# schematic.net
KiCad netlist of a schematic drawn in Altium Designer
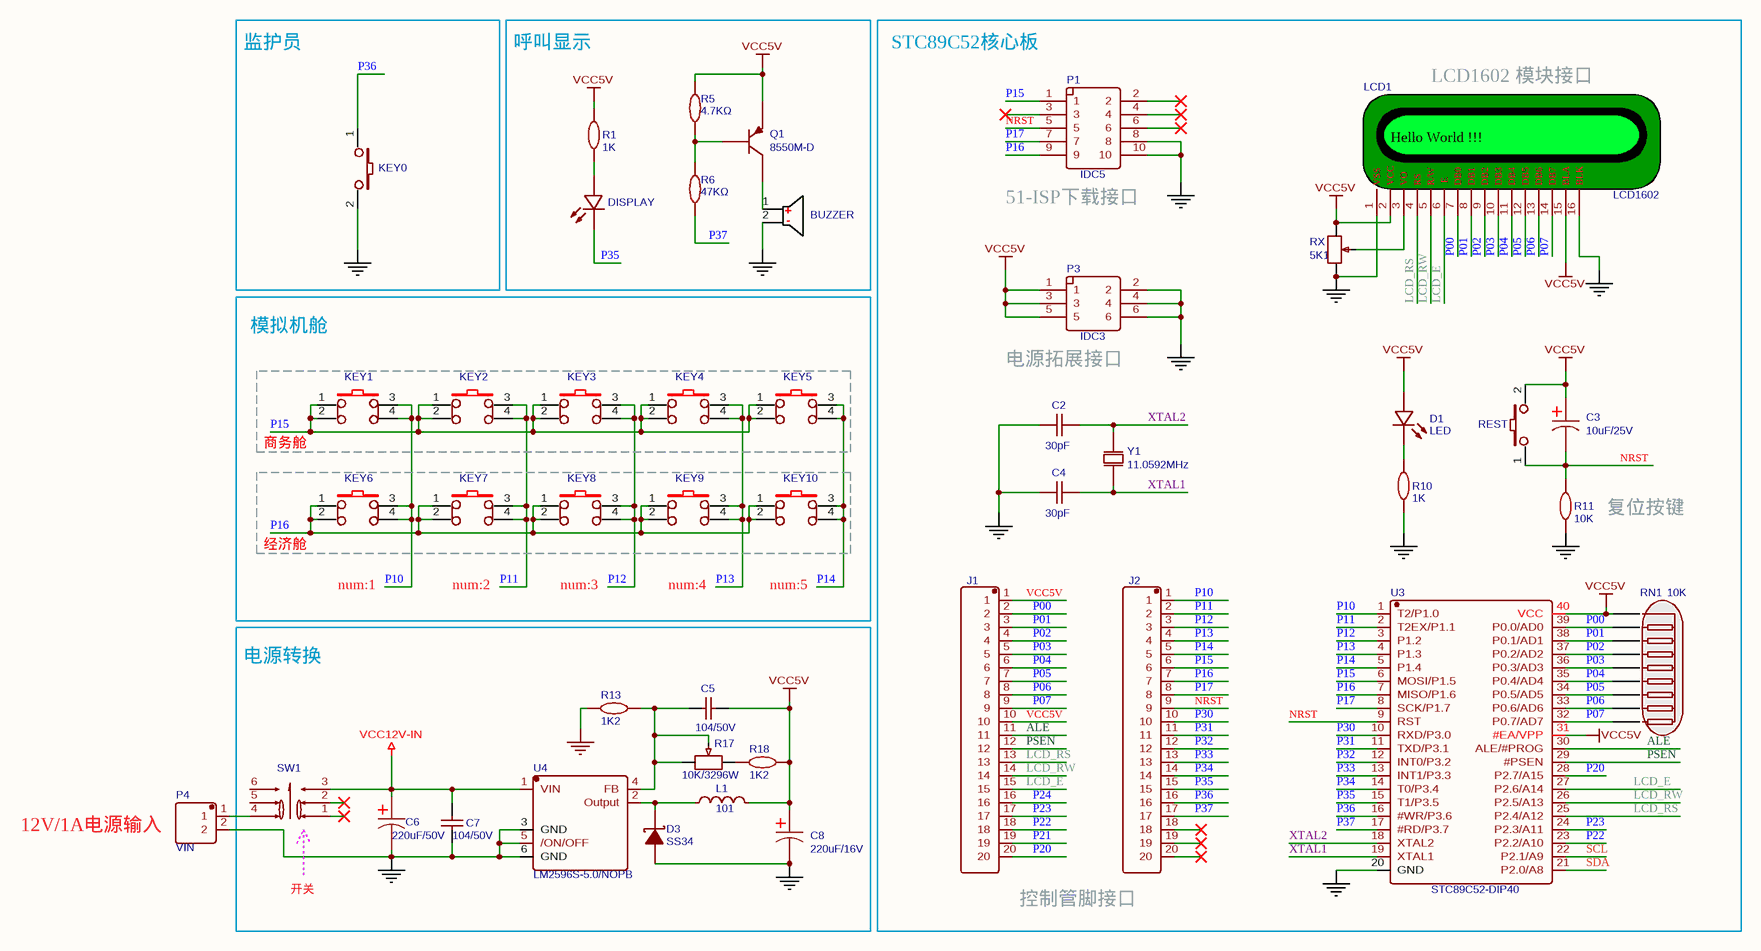
[diagram p0: schematic.schdoc]

(export (version "E")
  (design (tool "Eeschema 10.0.6"))
  (components
    (comp (ref "BUZZER")
      (value "C194267")
      (footprint "BEEP-TH_BD9.1-P5.00-D0.6-L-FD")
      (fields (field (name "CONTRIBUTOR") "LCSC"))
      (libsource (lib "altium-import") (part "root_0_C194267_"))
    )
    (comp (ref "C2")
      (value "30pF")
      (footprint "C0805")
      (fields
        (field (name "BOM_MANUFACTURER PART") "0805N220J500")
        (field (name "BOM_SUPPLIER PART") "C123642")
        (field (name "CONTRIBUTOR") "LCSC")
      )
      (libsource (lib "altium-import") (part "root_0_22pF_"))
    )
    (comp (ref "C3")
      (value "10uF/25V")
      (footprint "RAD6.3")
      (fields
        (field (name "BOM_SUPPLIER PART") "C140381")
        (field (name "BOM_MANUFACTURER PART") "CA45-B-10V-100uF-M")
        (field (name "CONTRIBUTOR") "LCSC")
      )
      (libsource (lib "Project") (part "100uF"))
    )
    (comp (ref "C4")
      (value "30pF")
      (footprint "C0805")
      (fields
        (field (name "BOM_MANUFACTURER PART") "0805N220J500")
        (field (name "BOM_SUPPLIER PART") "C123642")
        (field (name "CONTRIBUTOR") "LCSC")
      )
      (libsource (lib "altium-import") (part "root_0_22pF_"))
    )
    (comp (ref "C5")
      (value "104/50V")
      (footprint "C_0805")
      (fields
        (field (name "BOM_MANUFACTURER PART") "0805F104M500NT")
        (field (name "BOM_SUPPLIER PART") "C28378")
        (field (name "CONTRIBUTOR") "MrWangs")
      )
      (libsource (lib "altium-import") (part "root_0_100nF_"))
    )
    (comp (ref "C6")
      (value "220uF/50V")
      (footprint "RAD6.3")
      (fields
        (field (name "BOM_SUPPLIER PART") "C140381")
        (field (name "BOM_MANUFACTURER PART") "CA45-B-10V-100uF-M")
        (field (name "CONTRIBUTOR") "LCSC")
      )
      (libsource (lib "Project") (part "100uF"))
    )
    (comp (ref "C7")
      (value "104/50V")
      (footprint "C_0805")
      (fields
        (field (name "BOM_MANUFACTURER PART") "0805F104M500NT")
        (field (name "BOM_SUPPLIER PART") "C28378")
        (field (name "CONTRIBUTOR") "MrWangs")
      )
      (libsource (lib "altium-import") (part "root_3_100nF_"))
    )
    (comp (ref "C8")
      (value "220uF/16V")
      (footprint "CASE-B_3528")
      (fields
        (field (name "BOM_SUPPLIER PART") "C140381")
        (field (name "BOM_MANUFACTURER PART") "CA45-B-10V-100uF-M")
        (field (name "CONTRIBUTOR") "LCSC")
      )
      (libsource (lib "Project") (part "100uF"))
    )
    (comp (ref "D1")
      (value "LED")
      (footprint "LED-0805")
      (fields
        (field (name "BOM_MANUFACTURER PART") "whiteLEDSMD")
        (field (name "BOM_SUPPLIER PART") "C34499")
      )
      (libsource (lib "altium-import") (part "root_3_LEDSMD_"))
    )
    (comp (ref "D3")
      (value "SS34")
      (footprint "DO-214AC")
      (fields (field (name "BOM_SUPPLIER PART") "C266553") (field (name "CONTRIBUTOR") "LCSC"))
      (libsource (lib "altium-import") (part "root_1_SS34_C266553_"))
    )
    (comp (ref "DISPLAY")
      (value "HQ17-2102UWC")
      (footprint "LED0805-RD")
      (fields (field (name "BOM_SUPPLIER PART") "C154480") (field (name "CONTRIBUTOR") "LCSC"))
      (libsource (lib "altium-import") (part "root_1_HQ17-2102UWC_"))
    )
    (comp (ref "J1")
      (value "220S-1*20P H=8.5MM Ytype Gold-plated")
      (footprint "HDR-TH_20P-P2.54-V")
      (fields (field (name "BOM_SUPPLIER PART") "C124410") (field (name "CONTRIBUTOR") "LCSC"))
      (libsource (lib "altium-import") (part "root_0_220S-1*20P H=8.5MM Ytype Gold-plated_"))
    )
    (comp (ref "J2")
      (value "220S-1*20P H=8.5MM Ytype Gold-plated")
      (footprint "HDR-TH_20P-P2.54-V")
      (fields (field (name "BOM_SUPPLIER PART") "C124410") (field (name "CONTRIBUTOR") "LCSC"))
      (libsource (lib "altium-import") (part "root_0_220S-1*20P H=8.5MM Ytype Gold-plated_"))
    )
    (comp (ref "KEY0")
      (value "Switch3x4x2")
      (footprint "KEY-3.0*4.0")
      (fields (field (name "BOM_SUPPLIER PART") "C26638"))
      (libsource (lib "altium-import") (part "root_3_Switch3x4x2_"))
    )
    (comp (ref "KEY1")
      (value "12*12*5.5")
      (footprint "KEY-12*12-2")
      (fields (field (name "BOM_SUPPLIER PART") "C58359"))
      (libsource (lib "altium-import") (part "root_0_12*12*5.5_"))
    )
    (comp (ref "KEY2")
      (value "12*12*5.5")
      (footprint "KEY-12*12-2")
      (fields (field (name "BOM_SUPPLIER PART") "C58359"))
      (libsource (lib "altium-import") (part "root_0_12*12*5.5_"))
    )
    (comp (ref "KEY3")
      (value "12*12*5.5")
      (footprint "KEY-12*12-2")
      (fields (field (name "BOM_SUPPLIER PART") "C58359"))
      (libsource (lib "altium-import") (part "root_0_12*12*5.5_"))
    )
    (comp (ref "KEY4")
      (value "12*12*5.5")
      (footprint "KEY-12*12-2")
      (fields (field (name "BOM_SUPPLIER PART") "C58359"))
      (libsource (lib "altium-import") (part "root_0_12*12*5.5_"))
    )
    (comp (ref "KEY5")
      (value "12*12*5.5")
      (footprint "KEY-12*12-2")
      (fields (field (name "BOM_SUPPLIER PART") "C58359"))
      (libsource (lib "altium-import") (part "root_0_12*12*5.5_"))
    )
    (comp (ref "KEY6")
      (value "12*12*5.5")
      (footprint "KEY-12*12-2")
      (fields (field (name "BOM_SUPPLIER PART") "C58359"))
      (libsource (lib "altium-import") (part "root_0_12*12*5.5_"))
    )
    (comp (ref "KEY7")
      (value "12*12*5.5")
      (footprint "KEY-12*12-2")
      (fields (field (name "BOM_SUPPLIER PART") "C58359"))
      (libsource (lib "altium-import") (part "root_0_12*12*5.5_"))
    )
    (comp (ref "KEY8")
      (value "12*12*5.5")
      (footprint "KEY-12*12-2")
      (fields (field (name "BOM_SUPPLIER PART") "C58359"))
      (libsource (lib "altium-import") (part "root_0_12*12*5.5_"))
    )
    (comp (ref "KEY9")
      (value "12*12*5.5")
      (footprint "KEY-12*12-2")
      (fields (field (name "BOM_SUPPLIER PART") "C58359"))
      (libsource (lib "altium-import") (part "root_0_12*12*5.5_"))
    )
    (comp (ref "KEY10")
      (value "12*12*5.5")
      (footprint "KEY-12*12-2")
      (fields (field (name "BOM_SUPPLIER PART") "C58359"))
      (libsource (lib "altium-import") (part "root_0_12*12*5.5_"))
    )
    (comp (ref "L1")
      (value "101")
      (footprint "L-101-3A-SWB")
      (fields
        (field (name "BOM_MANUFACTURER PART") "BLM18RK102SN1D")
        (field (name "BOM_SUPPLIER PART") "C88986")
      )
      (libsource (lib "STM32F429BIT6_LIBRARY") (part "BLM18RK102SN1D"))
    )
    (comp (ref "LCD1")
      (value "LCD1602")
      (footprint "LCD1602")
      (fields
        (field (name "BOM_MANUFACTURER PART") "LCM1602K-NSW-BBW")
        (field (name "BOM_SUPPLIER PART") "C83275")
        (field (name "CONTRIBUTOR") "whwqm")
      )
      (libsource (lib "AT89S52核心板") (part "LCD1602"))
    )
    (comp (ref "P1")
      (value "IDC5")
      (footprint "IDC-TH_Z-231012810106")
      (fields
        (field (name "BOM_MANUFACTURER PART") "Z-231012810106")
        (field (name "BOM_SUPPLIER PART") "C93705")
      )
      (libsource (lib "altium-import") (part "root_0_Z-231012810106_"))
    )
    (comp (ref "P3")
      (value "IDC3")
      (footprint "IDC-TH_6P-P2.54_300R-6P")
      (fields
        (field (name "BOM_MANUFACTURER PART") "300R-6P")
        (field (name "BOM_SUPPLIER PART") "C146629")
        (field (name "CONTRIBUTOR") "LCSC")
      )
      (libsource (lib "altium-import") (part "root_0_300R-6P_"))
    )
    (comp (ref "P4")
      (value "VIN")
      (footprint "WJ2EDGR-5.08-2P")
      (fields
        (field (name "BOM_SUPPLIER PART") "C168673")
        (field (name "BOM_MANUFACTURER PART") "68000-102HLF")
        (field (name "CONTRIBUTOR") "LCSC")
      )
      (libsource (lib "MySheetLib") (part "WJ2EDGRC-5.08-2P"))
    )
    (comp (ref "Q1")
      (value "8550M-D")
      (footprint "SOT-23-3")
      (fields (field (name "BOM_SUPPLIER PART") "C305456") (field (name "CONTRIBUTOR") "LCSC"))
      (libsource (lib "Sheet_1") (part "8550M-D"))
    )
    (comp (ref "R1")
      (value "1K")
      (footprint "R0805")
      (fields
        (field (name "BOM_MANUFACTURER PART") "RK73H2ATTD1001F")
        (field (name "BOM_SUPPLIER PART") "C160065")
        (field (name "CONTRIBUTOR") "LCSC")
      )
      (libsource (lib "altium-import") (part "root_1_1K_"))
    )
    (comp (ref "R5")
      (value "4.7KΩ")
      (footprint "0805_R")
      (fields
        (field (name "BOM_SUPPLIER PART") "C237122")
        (field (name "BOM_MANUFACTURER PART") "RMCF0805FT100R")
        (field (name "CONTRIBUTOR") "MrWangs")
      )
      (libsource (lib "Project") (part "100"))
    )
    (comp (ref "R6")
      (value "47KΩ")
      (footprint "0805_R")
      (fields
        (field (name "BOM_SUPPLIER PART") "C237122")
        (field (name "BOM_MANUFACTURER PART") "RMCF0805FT100R")
        (field (name "CONTRIBUTOR") "MrWangs")
      )
      (libsource (lib "Project") (part "100"))
    )
    (comp (ref "R10")
      (value "1K")
      (footprint "R0805")
      (fields
        (field (name "BOM_MANUFACTURER PART") "RK73H2ATTD1001F")
        (field (name "BOM_SUPPLIER PART") "C160065")
        (field (name "CONTRIBUTOR") "LCSC")
      )
      (libsource (lib "altium-import") (part "root_1_1K_"))
    )
    (comp (ref "R11")
      (value "10K")
      (footprint "R0805")
      (fields
        (field (name "BOM_SUPPLIER PART") "C340510")
        (field (name "BOM_MANUFACTURER PART") "RMC1/10K203FTP")
        (field (name "CONTRIBUTOR") "LCSC")
      )
      (libsource (lib "altium-import") (part "root_1_10K_"))
    )
    (comp (ref "R13")
      (value "1K2")
      (footprint "R_0805")
      (fields
        (field (name "BOM_SUPPLIER PART") "C237122")
        (field (name "BOM_MANUFACTURER PART") "RMCF0805FT100R")
        (field (name "CONTRIBUTOR") "MrWangs")
      )
      (libsource (lib "MySheetLib") (part "R_0805"))
    )
    (comp (ref "R17")
      (value "10K/3296W")
      (footprint "RES-ADJ_3296W")
      (fields
        (field (name "BOM_MANUFACTURER PART") "3296W-1-500LF")
        (field (name "BOM_SUPPLIER PART") "C83692")
      )
      (libsource (lib "altium-import") (part "root_3_50_"))
    )
    (comp (ref "R18")
      (value "1K2")
      (footprint "R_0805")
      (fields
        (field (name "BOM_SUPPLIER PART") "C237122")
        (field (name "BOM_MANUFACTURER PART") "RMCF0805FT100R")
        (field (name "CONTRIBUTOR") "MrWangs")
      )
      (libsource (lib "MySheetLib") (part "R_0805"))
    )
    (comp (ref "REST")
      (value "Switch3x4x2")
      (footprint "KEY-3.0*4.0")
      (fields (field (name "BOM_SUPPLIER PART") "C26638"))
      (libsource (lib "altium-import") (part "root_1_Switch3x4x2_"))
    )
    (comp (ref "RN1")
      (value "10K")
      (footprint "RES-ARRAY-TH_9P-P2.54-D1.0")
      (fields (field (name "BOM_MANUFACTURER PART") "A09-121JP") (field (name "BOM_SUPPLIER PART") "C9110"))
      (libsource (lib "altium-import") (part "root_3_120_"))
    )
    (comp (ref "RX")
      (value "5K1")
      (footprint "RES-ADJ-SMD_EVM3ESX50B24")
      (fields
        (field (name "BOM_MANUFACTURER PART") "EVM3ESX50BY3")
        (field (name "BOM_SUPPLIER PART") "C11964")
      )
      (libsource (lib "altium-import") (part "root_2__"))
    )
    (comp (ref "SW1")
      (value "K8")
      (footprint "SW-TH_6P-L5.8-W5.8-P2.00-LS4.5-BL")
      (fields
        (field (name "BOM_MANUFACTURER PART") "K8-5851E-N1")
        (field (name "BOM_SUPPLIER PART") "C134191")
        (field (name "CONTRIBUTOR") "LCSC")
      )
      (libsource (lib "altium-import") (part "root_1_K8-5851E-N1_C134191_"))
    )
    (comp (ref "U3")
      (value "STC89C52-DIP40")
      (footprint "DIP-40_L52.3-W13.9-P2.54-LS15.2-BL")
      (fields
        (field (name "BOM_MANUFACTURER PART") "AT89S52-24PU")
        (field (name "BOM_SUPPLIER PART") "C9441")
      )
      (libsource (lib "altium-import") (part "root_0_AT89S52-24PU_"))
    )
    (comp (ref "U4")
      (value "LM2596S-5.0/NOPB")
      (footprint "TO-263-5")
      (fields (field (name "BOM_SUPPLIER PART") "C116713") (field (name "CONTRIBUTOR") "LCSC"))
      (libsource (lib "UsartControl") (part "LM2596S-5.0/NOPB"))
    )
    (comp (ref "Y1")
      (value "11.0592MHz")
      (footprint "HC-49S_L11.0-W4.6-P4.88")
      (fields
        (field (name "BOM_SUPPLIER PART") "C390747")
        (field (name "BOM_MANUFACTURER PART") "49SAC08000182060")
        (field (name "CONTRIBUTOR") "LCSC")
      )
      (libsource (lib "altium-import") (part "root_1_8MHZ_"))
    )
  )
  (nets
    (net (code "1") (name "/ALE") (class "Default")
      (node (ref "J1") (pin "11") (pinfunction "11_11") (pintype "passive"))
      (node (ref "U3") (pin "30") (pinfunction "ALE/#PROG_30") (pintype "passive"))
    )
    (net (code "2") (name "/LCD_E") (class "Default")
      (node (ref "J1") (pin "15") (pinfunction "15_15") (pintype "passive"))
      (node (ref "LCD1") (pin "6") (pinfunction "E_6") (pintype "passive"))
      (node (ref "U3") (pin "27") (pinfunction "P2.6/A14_27") (pintype "passive"))
    )
    (net (code "3") (name "/LCD_RS") (class "Default")
      (node (ref "J1") (pin "13") (pinfunction "13_13") (pintype "passive"))
      (node (ref "LCD1") (pin "4") (pinfunction "RS_4") (pintype "passive"))
      (node (ref "U3") (pin "25") (pinfunction "P2.4/A12_25") (pintype "passive"))
    )
    (net (code "4") (name "/LCD_RW") (class "Default")
      (node (ref "J1") (pin "14") (pinfunction "14_14") (pintype "passive"))
      (node (ref "LCD1") (pin "5") (pinfunction "R/W_5") (pintype "passive"))
      (node (ref "U3") (pin "26") (pinfunction "P2.5/A13_26") (pintype "passive"))
    )
    (net (code "5") (name "/NRST") (class "Default")
      (node (ref "C3") (pin "2") (pinfunction "2_2") (pintype "passive"))
      (node (ref "J2") (pin "9") (pinfunction "9_9") (pintype "passive"))
      (node (ref "P1") (pin "5") (pinfunction "5_5") (pintype "passive"))
      (node (ref "R11") (pin "2") (pinfunction "2_2") (pintype "passive"))
      (node (ref "REST") (pin "1") (pinfunction "1_1") (pintype "passive"))
      (node (ref "U3") (pin "9") (pinfunction "RST_9") (pintype "passive"))
    )
    (net (code "6") (name "/P00") (class "Default")
      (node (ref "J1") (pin "2") (pinfunction "2_2") (pintype "passive"))
      (node (ref "LCD1") (pin "7") (pinfunction "DB0_7") (pintype "passive"))
      (node (ref "RN1") (pin "2") (pinfunction "2_2") (pintype "passive"))
      (node (ref "U3") (pin "39") (pinfunction "P0.0/AD0_39") (pintype "passive"))
    )
    (net (code "7") (name "/P01") (class "Default")
      (node (ref "J1") (pin "3") (pinfunction "3_3") (pintype "passive"))
      (node (ref "LCD1") (pin "8") (pinfunction "DB1_8") (pintype "passive"))
      (node (ref "RN1") (pin "3") (pinfunction "3_3") (pintype "passive"))
      (node (ref "U3") (pin "38") (pinfunction "P0.1/AD1_38") (pintype "passive"))
    )
    (net (code "8") (name "/P02") (class "Default")
      (node (ref "J1") (pin "4") (pinfunction "4_4") (pintype "passive"))
      (node (ref "LCD1") (pin "9") (pinfunction "DB2_9") (pintype "passive"))
      (node (ref "RN1") (pin "4") (pinfunction "4_4") (pintype "passive"))
      (node (ref "U3") (pin "37") (pinfunction "P0.2/AD2_37") (pintype "passive"))
    )
    (net (code "9") (name "/P03") (class "Default")
      (node (ref "J1") (pin "5") (pinfunction "5_5") (pintype "passive"))
      (node (ref "LCD1") (pin "10") (pinfunction "DB3_10") (pintype "passive"))
      (node (ref "RN1") (pin "5") (pinfunction "5_5") (pintype "passive"))
      (node (ref "U3") (pin "36") (pinfunction "P0.3/AD3_36") (pintype "passive"))
    )
    (net (code "10") (name "/P04") (class "Default")
      (node (ref "J1") (pin "6") (pinfunction "6_6") (pintype "passive"))
      (node (ref "LCD1") (pin "11") (pinfunction "DB4_11") (pintype "passive"))
      (node (ref "RN1") (pin "6") (pinfunction "6_6") (pintype "passive"))
      (node (ref "U3") (pin "35") (pinfunction "P0.4/AD4_35") (pintype "passive"))
    )
    (net (code "11") (name "/P05") (class "Default")
      (node (ref "J1") (pin "7") (pinfunction "7_7") (pintype "passive"))
      (node (ref "LCD1") (pin "12") (pinfunction "DB5_12") (pintype "passive"))
      (node (ref "RN1") (pin "7") (pinfunction "7_7") (pintype "passive"))
      (node (ref "U3") (pin "34") (pinfunction "P0.5/AD5_34") (pintype "passive"))
    )
    (net (code "12") (name "/P06") (class "Default")
      (node (ref "J1") (pin "8") (pinfunction "8_8") (pintype "passive"))
      (node (ref "LCD1") (pin "13") (pinfunction "DB6_13") (pintype "passive"))
      (node (ref "RN1") (pin "8") (pinfunction "8_8") (pintype "passive"))
      (node (ref "U3") (pin "33") (pinfunction "P0.6/AD6_33") (pintype "passive"))
    )
    (net (code "13") (name "/P07") (class "Default")
      (node (ref "J1") (pin "9") (pinfunction "9_9") (pintype "passive"))
      (node (ref "LCD1") (pin "14") (pinfunction "DB7_14") (pintype "passive"))
      (node (ref "RN1") (pin "9") (pinfunction "9_9") (pintype "passive"))
      (node (ref "U3") (pin "32") (pinfunction "P0.7/AD7_32") (pintype "passive"))
    )
    (net (code "14") (name "/P10") (class "Default")
      (node (ref "J2") (pin "1") (pinfunction "1_1") (pintype "passive"))
      (node (ref "KEY1") (pin "3") (pinfunction "3_3") (pintype "passive"))
      (node (ref "KEY1") (pin "4") (pinfunction "4_4") (pintype "passive"))
      (node (ref "KEY6") (pin "3") (pinfunction "3_3") (pintype "passive"))
      (node (ref "KEY6") (pin "4") (pinfunction "4_4") (pintype "passive"))
      (node (ref "U3") (pin "1") (pinfunction "T2/P1.0_1") (pintype "passive"))
    )
    (net (code "15") (name "/P11") (class "Default")
      (node (ref "J2") (pin "2") (pinfunction "2_2") (pintype "passive"))
      (node (ref "KEY2") (pin "3") (pinfunction "3_3") (pintype "passive"))
      (node (ref "KEY2") (pin "4") (pinfunction "4_4") (pintype "passive"))
      (node (ref "KEY7") (pin "3") (pinfunction "3_3") (pintype "passive"))
      (node (ref "KEY7") (pin "4") (pinfunction "4_4") (pintype "passive"))
      (node (ref "U3") (pin "2") (pinfunction "T2EX/P1.1_2") (pintype "passive"))
    )
    (net (code "16") (name "/P12") (class "Default")
      (node (ref "J2") (pin "3") (pinfunction "3_3") (pintype "passive"))
      (node (ref "KEY3") (pin "3") (pinfunction "3_3") (pintype "passive"))
      (node (ref "KEY3") (pin "4") (pinfunction "4_4") (pintype "passive"))
      (node (ref "KEY8") (pin "3") (pinfunction "3_3") (pintype "passive"))
      (node (ref "KEY8") (pin "4") (pinfunction "4_4") (pintype "passive"))
      (node (ref "U3") (pin "3") (pinfunction "P1.2_3") (pintype "passive"))
    )
    (net (code "17") (name "/P13") (class "Default")
      (node (ref "J2") (pin "4") (pinfunction "4_4") (pintype "passive"))
      (node (ref "KEY4") (pin "3") (pinfunction "3_3") (pintype "passive"))
      (node (ref "KEY4") (pin "4") (pinfunction "4_4") (pintype "passive"))
      (node (ref "KEY9") (pin "3") (pinfunction "3_3") (pintype "passive"))
      (node (ref "KEY9") (pin "4") (pinfunction "4_4") (pintype "passive"))
      (node (ref "U3") (pin "4") (pinfunction "P1.3_4") (pintype "passive"))
    )
    (net (code "18") (name "/P14") (class "Default")
      (node (ref "J2") (pin "5") (pinfunction "5_5") (pintype "passive"))
      (node (ref "KEY10") (pin "3") (pinfunction "3_3") (pintype "passive"))
      (node (ref "KEY10") (pin "4") (pinfunction "4_4") (pintype "passive"))
      (node (ref "KEY5") (pin "3") (pinfunction "3_3") (pintype "passive"))
      (node (ref "KEY5") (pin "4") (pinfunction "4_4") (pintype "passive"))
      (node (ref "U3") (pin "5") (pinfunction "P1.4_5") (pintype "passive"))
    )
    (net (code "19") (name "/P15") (class "Default")
      (node (ref "J2") (pin "6") (pinfunction "6_6") (pintype "passive"))
      (node (ref "KEY1") (pin "1") (pinfunction "1_1") (pintype "passive"))
      (node (ref "KEY1") (pin "2") (pinfunction "2_2") (pintype "passive"))
      (node (ref "KEY2") (pin "1") (pinfunction "1_1") (pintype "passive"))
      (node (ref "KEY2") (pin "2") (pinfunction "2_2") (pintype "passive"))
      (node (ref "KEY3") (pin "1") (pinfunction "1_1") (pintype "passive"))
      (node (ref "KEY3") (pin "2") (pinfunction "2_2") (pintype "passive"))
      (node (ref "KEY4") (pin "1") (pinfunction "1_1") (pintype "passive"))
      (node (ref "KEY4") (pin "2") (pinfunction "2_2") (pintype "passive"))
      (node (ref "KEY5") (pin "1") (pinfunction "1_1") (pintype "passive"))
      (node (ref "KEY5") (pin "2") (pinfunction "2_2") (pintype "passive"))
      (node (ref "P1") (pin "1") (pinfunction "1_1") (pintype "passive"))
      (node (ref "U3") (pin "6") (pinfunction "MOSI/P1.5_6") (pintype "passive"))
    )
    (net (code "20") (name "/P16") (class "Default")
      (node (ref "J2") (pin "7") (pinfunction "7_7") (pintype "passive"))
      (node (ref "KEY10") (pin "1") (pinfunction "1_1") (pintype "passive"))
      (node (ref "KEY10") (pin "2") (pinfunction "2_2") (pintype "passive"))
      (node (ref "KEY6") (pin "1") (pinfunction "1_1") (pintype "passive"))
      (node (ref "KEY6") (pin "2") (pinfunction "2_2") (pintype "passive"))
      (node (ref "KEY7") (pin "1") (pinfunction "1_1") (pintype "passive"))
      (node (ref "KEY7") (pin "2") (pinfunction "2_2") (pintype "passive"))
      (node (ref "KEY8") (pin "1") (pinfunction "1_1") (pintype "passive"))
      (node (ref "KEY8") (pin "2") (pinfunction "2_2") (pintype "passive"))
      (node (ref "KEY9") (pin "1") (pinfunction "1_1") (pintype "passive"))
      (node (ref "KEY9") (pin "2") (pinfunction "2_2") (pintype "passive"))
      (node (ref "P1") (pin "9") (pinfunction "9_9") (pintype "passive"))
      (node (ref "U3") (pin "7") (pinfunction "MISO/P1.6_7") (pintype "passive"))
    )
    (net (code "21") (name "/P17") (class "Default")
      (node (ref "J2") (pin "8") (pinfunction "8_8") (pintype "passive"))
      (node (ref "P1") (pin "7") (pinfunction "7_7") (pintype "passive"))
      (node (ref "U3") (pin "8") (pinfunction "SCK/P1.7_8") (pintype "passive"))
    )
    (net (code "22") (name "/P20") (class "Default")
      (node (ref "J1") (pin "20") (pinfunction "20_20") (pintype "passive"))
      (node (ref "U3") (pin "28") (pinfunction "P2.7/A15_28") (pintype "passive"))
    )
    (net (code "23") (name "/P21") (class "Default")
      (node (ref "J1") (pin "19") (pinfunction "19_19") (pintype "passive"))
    )
    (net (code "24") (name "/P22") (class "Default")
      (node (ref "J1") (pin "18") (pinfunction "18_18") (pintype "passive"))
      (node (ref "U3") (pin "23") (pinfunction "P2.2/A10_23") (pintype "passive"))
    )
    (net (code "25") (name "/P23") (class "Default")
      (node (ref "J1") (pin "17") (pinfunction "17_17") (pintype "passive"))
      (node (ref "U3") (pin "24") (pinfunction "P2.3/A11_24") (pintype "passive"))
    )
    (net (code "26") (name "/P24") (class "Default")
      (node (ref "J1") (pin "16") (pinfunction "16_16") (pintype "passive"))
    )
    (net (code "27") (name "/P30") (class "Default")
      (node (ref "J2") (pin "10") (pinfunction "10_10") (pintype "passive"))
      (node (ref "U3") (pin "10") (pinfunction "RXD/P3.0_10") (pintype "passive"))
    )
    (net (code "28") (name "/P31") (class "Default")
      (node (ref "J2") (pin "11") (pinfunction "11_11") (pintype "passive"))
      (node (ref "U3") (pin "11") (pinfunction "TXD/P3.1_11") (pintype "passive"))
    )
    (net (code "29") (name "/P32") (class "Default")
      (node (ref "J2") (pin "12") (pinfunction "12_12") (pintype "passive"))
      (node (ref "U3") (pin "12") (pinfunction "INT0/P3.2_12") (pintype "passive"))
    )
    (net (code "30") (name "/P33") (class "Default")
      (node (ref "J2") (pin "13") (pinfunction "13_13") (pintype "passive"))
      (node (ref "U3") (pin "13") (pinfunction "INT1/P3.3_13") (pintype "passive"))
    )
    (net (code "31") (name "/P34") (class "Default")
      (node (ref "J2") (pin "14") (pinfunction "14_14") (pintype "passive"))
      (node (ref "U3") (pin "14") (pinfunction "T0/P3.4_14") (pintype "passive"))
    )
    (net (code "32") (name "/P35") (class "Default")
      (node (ref "DISPLAY") (pin "1") (pinfunction "K_1") (pintype "passive"))
      (node (ref "J2") (pin "15") (pinfunction "15_15") (pintype "passive"))
      (node (ref "U3") (pin "15") (pinfunction "T1/P3.5_15") (pintype "passive"))
    )
    (net (code "33") (name "/P36") (class "Default")
      (node (ref "J2") (pin "16") (pinfunction "16_16") (pintype "passive"))
      (node (ref "KEY0") (pin "1") (pinfunction "1_1") (pintype "passive"))
      (node (ref "U3") (pin "16") (pinfunction "#WR/P3.6_16") (pintype "passive"))
    )
    (net (code "34") (name "/P37") (class "Default")
      (node (ref "J2") (pin "17") (pinfunction "17_17") (pintype "passive"))
      (node (ref "R6") (pin "1") (pinfunction "1_1") (pintype "passive"))
      (node (ref "U3") (pin "17") (pinfunction "#RD/P3.7_17") (pintype "passive"))
    )
    (net (code "35") (name "/PSEN") (class "Default")
      (node (ref "J1") (pin "12") (pinfunction "12_12") (pintype "passive"))
      (node (ref "U3") (pin "29") (pinfunction "#PSEN_29") (pintype "passive"))
    )
    (net (code "36") (name "/SCL") (class "Default")
      (node (ref "U3") (pin "22") (pinfunction "P2.1/A9_22") (pintype "passive"))
    )
    (net (code "37") (name "/SDA") (class "Default")
      (node (ref "U3") (pin "21") (pinfunction "P2.0/A8_21") (pintype "passive"))
    )
    (net (code "38") (name "/XTAL1") (class "Default")
      (node (ref "C4") (pin "2") (pinfunction "2_2") (pintype "passive"))
      (node (ref "U3") (pin "19") (pinfunction "XTAL1_19") (pintype "passive"))
      (node (ref "Y1") (pin "1") (pinfunction "OSC1_1") (pintype "passive"))
    )
    (net (code "39") (name "/XTAL2") (class "Default")
      (node (ref "C2") (pin "2") (pinfunction "2_2") (pintype "passive"))
      (node (ref "U3") (pin "18") (pinfunction "XTAL2_18") (pintype "passive"))
      (node (ref "Y1") (pin "2") (pinfunction "OSC2_2") (pintype "passive"))
    )
    (net (code "40") (name "GND") (class "Default")
      (node (ref "BUZZER") (pin "2") (pinfunction "2_2") (pintype "passive"))
      (node (ref "C2") (pin "1") (pinfunction "1_1") (pintype "passive"))
      (node (ref "C4") (pin "1") (pinfunction "1_1") (pintype "passive"))
      (node (ref "C6") (pin "2") (pinfunction "2_2") (pintype "passive"))
      (node (ref "C7") (pin "2") (pinfunction "2_2") (pintype "passive"))
      (node (ref "C8") (pin "2") (pinfunction "2_2") (pintype "passive"))
      (node (ref "D3") (pin "1") (pinfunction "A_1") (pintype "passive"))
      (node (ref "KEY0") (pin "2") (pinfunction "2_2") (pintype "passive"))
      (node (ref "LCD1") (pin "1") (pinfunction "VSS_1") (pintype "passive"))
      (node (ref "LCD1") (pin "16") (pinfunction "BLK_16") (pintype "passive"))
      (node (ref "P1") (pin "10") (pinfunction "10_10") (pintype "passive"))
      (node (ref "P1") (pin "8") (pinfunction "8_8") (pintype "passive"))
      (node (ref "P3") (pin "2") (pinfunction "2_2") (pintype "passive"))
      (node (ref "P3") (pin "4") (pinfunction "4_4") (pintype "passive"))
      (node (ref "P3") (pin "6") (pinfunction "6_6") (pintype "passive"))
      (node (ref "P4") (pin "2") (pinfunction "2_2") (pintype "passive"))
      (node (ref "R10") (pin "1") (pinfunction "1_1") (pintype "passive"))
      (node (ref "R11") (pin "1") (pinfunction "1_1") (pintype "passive"))
      (node (ref "R13") (pin "2") (pinfunction "2_2") (pintype "passive"))
      (node (ref "RX") (pin "1") (pinfunction "1_1") (pintype "passive"))
      (node (ref "U3") (pin "20") (pinfunction "GND_20") (pintype "passive"))
      (node (ref "U4") (pin "3") (pinfunction "GND_3") (pintype "passive"))
      (node (ref "U4") (pin "5") (pinfunction "/ON/OFF_5") (pintype "passive"))
      (node (ref "U4") (pin "6") (pinfunction "GND_6") (pintype "passive"))
    )
    (net (code "41") (name "Net-(D1-K)") (class "Default")
      (node (ref "D1") (pin "2") (pinfunction "K_2") (pintype "passive"))
      (node (ref "R10") (pin "2") (pinfunction "2_2") (pintype "passive"))
    )
    (net (code "42") (name "Net-(D3-K)") (class "Default")
      (node (ref "D3") (pin "2") (pinfunction "K_2") (pintype "passive"))
      (node (ref "L1") (pin "1") (pinfunction "1_1") (pintype "passive"))
      (node (ref "U4") (pin "2") (pinfunction "Output_2") (pintype "passive"))
    )
    (net (code "43") (name "Net-(DISPLAY-A)") (class "Default")
      (node (ref "DISPLAY") (pin "2") (pinfunction "A_2") (pintype "passive"))
      (node (ref "R1") (pin "1") (pinfunction "1_1") (pintype "passive"))
    )
    (net (code "44") (name "Net-(LCD1-VO)") (class "Default")
      (node (ref "LCD1") (pin "3") (pinfunction "VO_3") (pintype "passive"))
      (node (ref "RX") (pin "2") (pinfunction "2_2") (pintype "passive"))
    )
    (net (code "45") (name "Net-(P4-Pad1)") (class "Default")
      (node (ref "P4") (pin "1") (pinfunction "1_1") (pintype "passive"))
      (node (ref "SW1") (pin "4") (pinfunction "4_4") (pintype "passive"))
    )
    (net (code "46") (name "Net-(Q1-B)") (class "Default")
      (node (ref "Q1") (pin "1") (pinfunction "B_1") (pintype "passive"))
      (node (ref "R5") (pin "1") (pinfunction "1_1") (pintype "passive"))
      (node (ref "R6") (pin "2") (pinfunction "2_2") (pintype "passive"))
    )
    (net (code "47") (name "Net-(Q1-C)") (class "Default")
      (node (ref "BUZZER") (pin "1") (pinfunction "1_1") (pintype "passive"))
      (node (ref "Q1") (pin "3") (pinfunction "C_3") (pintype "passive"))
    )
    (net (code "48") (name "Net-(R17-Pad1)") (class "Default")
      (node (ref "R17") (pin "1") (pinfunction "1_1") (pintype "passive"))
      (node (ref "R18") (pin "2") (pinfunction "2_2") (pintype "passive"))
    )
    (net (code "49") (name "Net-(U4-FB)") (class "Default")
      (node (ref "C5") (pin "1") (pinfunction "1_1") (pintype "passive"))
      (node (ref "R13") (pin "1") (pinfunction "1_1") (pintype "passive"))
      (node (ref "R17") (pin "2") (pinfunction "2_2") (pintype "passive"))
      (node (ref "R17") (pin "3") (pinfunction "3_3") (pintype "passive"))
      (node (ref "U4") (pin "4") (pinfunction "FB_4") (pintype "passive"))
    )
    (net (code "50") (name "VCC5V") (class "Default")
      (node (ref "C3") (pin "1") (pinfunction "1_1") (pintype "passive"))
      (node (ref "C5") (pin "2") (pinfunction "2_2") (pintype "passive"))
      (node (ref "C8") (pin "1") (pinfunction "1_1") (pintype "passive"))
      (node (ref "D1") (pin "1") (pinfunction "A_1") (pintype "passive"))
      (node (ref "J1") (pin "1") (pinfunction "1_1") (pintype "passive"))
      (node (ref "J1") (pin "10") (pinfunction "10_10") (pintype "passive"))
      (node (ref "L1") (pin "2") (pinfunction "2_2") (pintype "passive"))
      (node (ref "LCD1") (pin "15") (pinfunction "BLA_15") (pintype "passive"))
      (node (ref "LCD1") (pin "2") (pinfunction "VCC_2") (pintype "passive"))
      (node (ref "P3") (pin "1") (pinfunction "1_1") (pintype "passive"))
      (node (ref "P3") (pin "3") (pinfunction "3_3") (pintype "passive"))
      (node (ref "P3") (pin "5") (pinfunction "5_5") (pintype "passive"))
      (node (ref "Q1") (pin "2") (pinfunction "E_2") (pintype "passive"))
      (node (ref "R1") (pin "2") (pinfunction "2_2") (pintype "passive"))
      (node (ref "R18") (pin "1") (pinfunction "1_1") (pintype "passive"))
      (node (ref "R5") (pin "2") (pinfunction "2_2") (pintype "passive"))
      (node (ref "REST") (pin "2") (pinfunction "2_2") (pintype "passive"))
      (node (ref "RN1") (pin "1") (pinfunction "1_1") (pintype "passive"))
      (node (ref "RX") (pin "3") (pinfunction "3_3") (pintype "passive"))
      (node (ref "U3") (pin "31") (pinfunction "#EA/VPP_31") (pintype "passive"))
      (node (ref "U3") (pin "40") (pinfunction "VCC_40") (pintype "passive"))
    )
    (net (code "51") (name "VCC12V-IN") (class "Default")
      (node (ref "C6") (pin "1") (pinfunction "1_1") (pintype "passive"))
      (node (ref "C7") (pin "1") (pinfunction "1_1") (pintype "passive"))
      (node (ref "SW1") (pin "3") (pinfunction "3_3") (pintype "passive"))
      (node (ref "U4") (pin "1") (pinfunction "VIN_1") (pintype "passive"))
    )
    (net (code "52") (name "unconnected-(J2-Pad18)") (class "Default")
      (node (ref "J2") (pin "18") (pinfunction "18_18") (pintype "passive+no_connect"))
    )
    (net (code "53") (name "unconnected-(J2-Pad19)") (class "Default")
      (node (ref "J2") (pin "19") (pinfunction "19_19") (pintype "passive+no_connect"))
    )
    (net (code "54") (name "unconnected-(J2-Pad20)") (class "Default")
      (node (ref "J2") (pin "20") (pinfunction "20_20") (pintype "passive+no_connect"))
    )
    (net (code "55") (name "unconnected-(P1-Pad2)") (class "Default")
      (node (ref "P1") (pin "2") (pinfunction "2_2") (pintype "passive+no_connect"))
    )
    (net (code "56") (name "unconnected-(P1-Pad3)") (class "Default")
      (node (ref "P1") (pin "3") (pinfunction "3_3") (pintype "passive+no_connect"))
    )
    (net (code "57") (name "unconnected-(P1-Pad4)") (class "Default")
      (node (ref "P1") (pin "4") (pinfunction "4_4") (pintype "passive+no_connect"))
    )
    (net (code "58") (name "unconnected-(P1-Pad6)") (class "Default")
      (node (ref "P1") (pin "6") (pinfunction "6_6") (pintype "passive+no_connect"))
    )
    (net (code "59") (name "unconnected-(SW1-Pad1)") (class "Default")
      (node (ref "SW1") (pin "1") (pinfunction "1_1") (pintype "passive+no_connect"))
    )
    (net (code "60") (name "unconnected-(SW1-Pad2)") (class "Default")
      (node (ref "SW1") (pin "2") (pinfunction "2_2") (pintype "passive+no_connect"))
    )
    (net (code "61") (name "unconnected-(SW1-Pad5)") (class "Default")
      (node (ref "SW1") (pin "5") (pinfunction "5_5") (pintype "passive"))
    )
    (net (code "62") (name "unconnected-(SW1-Pad6)") (class "Default")
      (node (ref "SW1") (pin "6") (pinfunction "6_6") (pintype "passive"))
    )
  )
)
